# ProDoc_Schematic1_2025-02-16.net
KiCad netlist of a schematic drawn in EasyEDA Pro
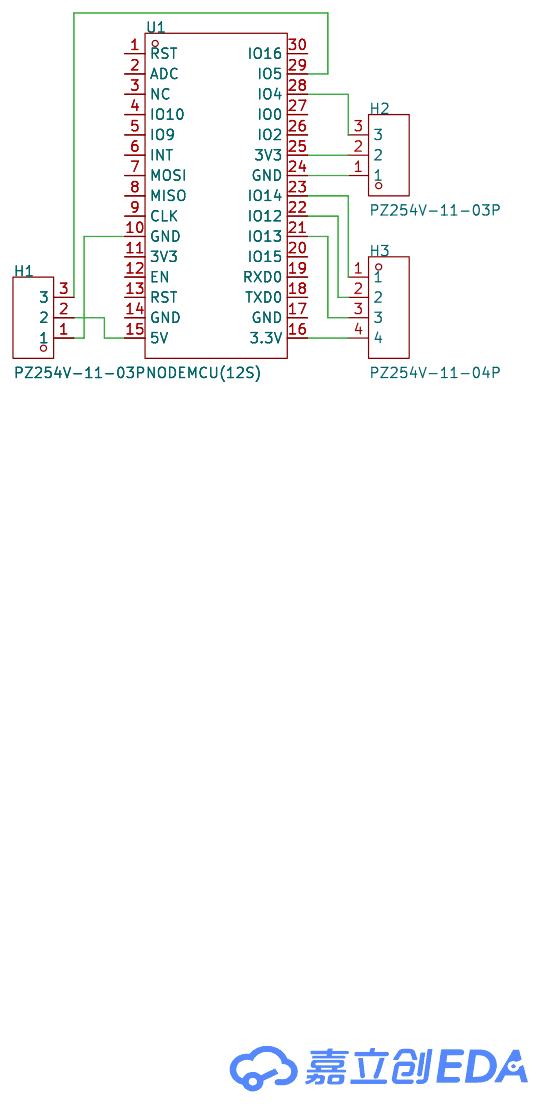
[diagram p0: schematic sheet]

(export (version "E")
  (design (tool "Eeschema 10.0.6"))
  (components
    (comp (ref "H1")
      (value "PZ254V-11-03P")
      (footprint "easyedapro:HDR-TH_3P-P2.54-V-M")
      (fields (field (name "Manufacturer") "XFCN(兴飞)"))
      (libsource (lib "easyedapro") (part "PZ254V-11-03P_C2937625"))
    )
    (comp (ref "H2")
      (value "PZ254V-11-03P")
      (footprint "easyedapro:HDR-TH_3P-P2.54-V-M")
      (fields (field (name "Manufacturer") "XFCN(兴飞)"))
      (libsource (lib "easyedapro") (part "PZ254V-11-03P_C2937625"))
    )
    (comp (ref "H3")
      (value "PZ254V-11-04P")
      (footprint "easyedapro:HDR-TH_4P-P2.54-V-M")
      (fields (field (name "Manufacturer") "XFCN(兴飞)"))
      (libsource (lib "easyedapro") (part "PZ254V-11-04P_C2691448"))
    )
    (comp (ref "U1")
      (value "NODEMCU(12S)")
      (footprint "easyedapro:COMM-TH_L43.7-W25.4-P2.54_NODEMCU")
      (description "处理器:-;运行内存:-;USB:-;WIFI协议:-;蓝牙:-;以太网:-;")
      (fields (field (name "Manufacturer") "Ai-Thinker(安信可)"))
      (libsource (lib "easyedapro") (part "NODEMCU(12S)"))
    )
  )
  (nets
    (net (code "1") (name "Net-(H1-Pad1)") (class "Default")
      (node (ref "H1") (pin "1") (pinfunction "1_1") (pintype "unspecified"))
      (node (ref "U1") (pin "10") (pinfunction "GND_10") (pintype "unspecified"))
    )
    (net (code "2") (name "Net-(H2-Pad1)") (class "Default")
      (node (ref "H2") (pin "1") (pinfunction "1_1") (pintype "unspecified"))
      (node (ref "U1") (pin "24") (pinfunction "GND_24") (pintype "unspecified"))
    )
    (net (code "3") (name "Net-(H2-Pad2)") (class "Default")
      (node (ref "H2") (pin "2") (pinfunction "2_2") (pintype "unspecified"))
      (node (ref "U1") (pin "25") (pinfunction "3V3_25") (pintype "unspecified"))
    )
    (net (code "4") (name "Net-(U1-3.3V)") (class "Default")
      (node (ref "H3") (pin "4") (pinfunction "4_4") (pintype "unspecified"))
      (node (ref "U1") (pin "16") (pinfunction "3.3V_16") (pintype "unspecified"))
    )
    (net (code "5") (name "Net-(U1-5V)") (class "Default")
      (node (ref "H1") (pin "2") (pinfunction "2_2") (pintype "unspecified"))
      (node (ref "U1") (pin "15") (pinfunction "5V_15") (pintype "unspecified"))
    )
    (net (code "6") (name "Net-(U1-IO4)") (class "Default")
      (node (ref "H2") (pin "3") (pinfunction "3_3") (pintype "unspecified"))
      (node (ref "U1") (pin "28") (pinfunction "IO4_28") (pintype "unspecified"))
    )
    (net (code "7") (name "Net-(U1-IO5)") (class "Default")
      (node (ref "H1") (pin "3") (pinfunction "3_3") (pintype "unspecified"))
      (node (ref "U1") (pin "29") (pinfunction "IO5_29") (pintype "unspecified"))
    )
    (net (code "8") (name "Net-(U1-IO12)") (class "Default")
      (node (ref "H3") (pin "2") (pinfunction "2_2") (pintype "unspecified"))
      (node (ref "U1") (pin "22") (pinfunction "IO12_22") (pintype "unspecified"))
    )
    (net (code "9") (name "Net-(U1-IO13)") (class "Default")
      (node (ref "H3") (pin "3") (pinfunction "3_3") (pintype "unspecified"))
      (node (ref "U1") (pin "21") (pinfunction "IO13_21") (pintype "unspecified"))
    )
    (net (code "10") (name "Net-(U1-IO14)") (class "Default")
      (node (ref "H3") (pin "1") (pinfunction "1_1") (pintype "unspecified"))
      (node (ref "U1") (pin "23") (pinfunction "IO14_23") (pintype "unspecified"))
    )
    (net (code "11") (name "unconnected-(U1-3V3-Pad11)") (class "Default")
      (node (ref "U1") (pin "11") (pinfunction "3V3_11") (pintype "unspecified"))
    )
    (net (code "12") (name "unconnected-(U1-ADC-Pad2)") (class "Default")
      (node (ref "U1") (pin "2") (pinfunction "ADC_2") (pintype "unspecified"))
    )
    (net (code "13") (name "unconnected-(U1-CLK-Pad9)") (class "Default")
      (node (ref "U1") (pin "9") (pinfunction "CLK_9") (pintype "unspecified"))
    )
    (net (code "14") (name "unconnected-(U1-EN-Pad12)") (class "Default")
      (node (ref "U1") (pin "12") (pinfunction "EN_12") (pintype "unspecified"))
    )
    (net (code "15") (name "unconnected-(U1-GND-Pad14)") (class "Default")
      (node (ref "U1") (pin "14") (pinfunction "GND_14") (pintype "unspecified"))
    )
    (net (code "16") (name "unconnected-(U1-GND-Pad17)") (class "Default")
      (node (ref "U1") (pin "17") (pinfunction "GND_17") (pintype "unspecified"))
    )
    (net (code "17") (name "unconnected-(U1-INT-Pad6)") (class "Default")
      (node (ref "U1") (pin "6") (pinfunction "INT_6") (pintype "unspecified"))
    )
    (net (code "18") (name "unconnected-(U1-IO0-Pad27)") (class "Default")
      (node (ref "U1") (pin "27") (pinfunction "IO0_27") (pintype "unspecified"))
    )
    (net (code "19") (name "unconnected-(U1-IO2-Pad26)") (class "Default")
      (node (ref "U1") (pin "26") (pinfunction "IO2_26") (pintype "unspecified"))
    )
    (net (code "20") (name "unconnected-(U1-IO9-Pad5)") (class "Default")
      (node (ref "U1") (pin "5") (pinfunction "IO9_5") (pintype "unspecified"))
    )
    (net (code "21") (name "unconnected-(U1-IO10-Pad4)") (class "Default")
      (node (ref "U1") (pin "4") (pinfunction "IO10_4") (pintype "unspecified"))
    )
    (net (code "22") (name "unconnected-(U1-IO15-Pad20)") (class "Default")
      (node (ref "U1") (pin "20") (pinfunction "IO15_20") (pintype "unspecified"))
    )
    (net (code "23") (name "unconnected-(U1-IO16-Pad30)") (class "Default")
      (node (ref "U1") (pin "30") (pinfunction "IO16_30") (pintype "unspecified"))
    )
    (net (code "24") (name "unconnected-(U1-MISO-Pad8)") (class "Default")
      (node (ref "U1") (pin "8") (pinfunction "MISO_8") (pintype "unspecified"))
    )
    (net (code "25") (name "unconnected-(U1-MOSI-Pad7)") (class "Default")
      (node (ref "U1") (pin "7") (pinfunction "MOSI_7") (pintype "unspecified"))
    )
    (net (code "26") (name "unconnected-(U1-NC-Pad3)") (class "Default")
      (node (ref "U1") (pin "3") (pinfunction "NC_3") (pintype "unspecified"))
    )
    (net (code "27") (name "unconnected-(U1-RST-Pad1)") (class "Default")
      (node (ref "U1") (pin "1") (pinfunction "RST_1") (pintype "unspecified"))
    )
    (net (code "28") (name "unconnected-(U1-RST-Pad13)") (class "Default")
      (node (ref "U1") (pin "13") (pinfunction "RST_13") (pintype "unspecified"))
    )
    (net (code "29") (name "unconnected-(U1-RXD0-Pad19)") (class "Default")
      (node (ref "U1") (pin "19") (pinfunction "RXD0_19") (pintype "unspecified"))
    )
    (net (code "30") (name "unconnected-(U1-TXD0-Pad18)") (class "Default")
      (node (ref "U1") (pin "18") (pinfunction "TXD0_18") (pintype "unspecified"))
    )
  )
)
